# rotor.net
KiCad netlist of a schematic drawn in Altium Designer
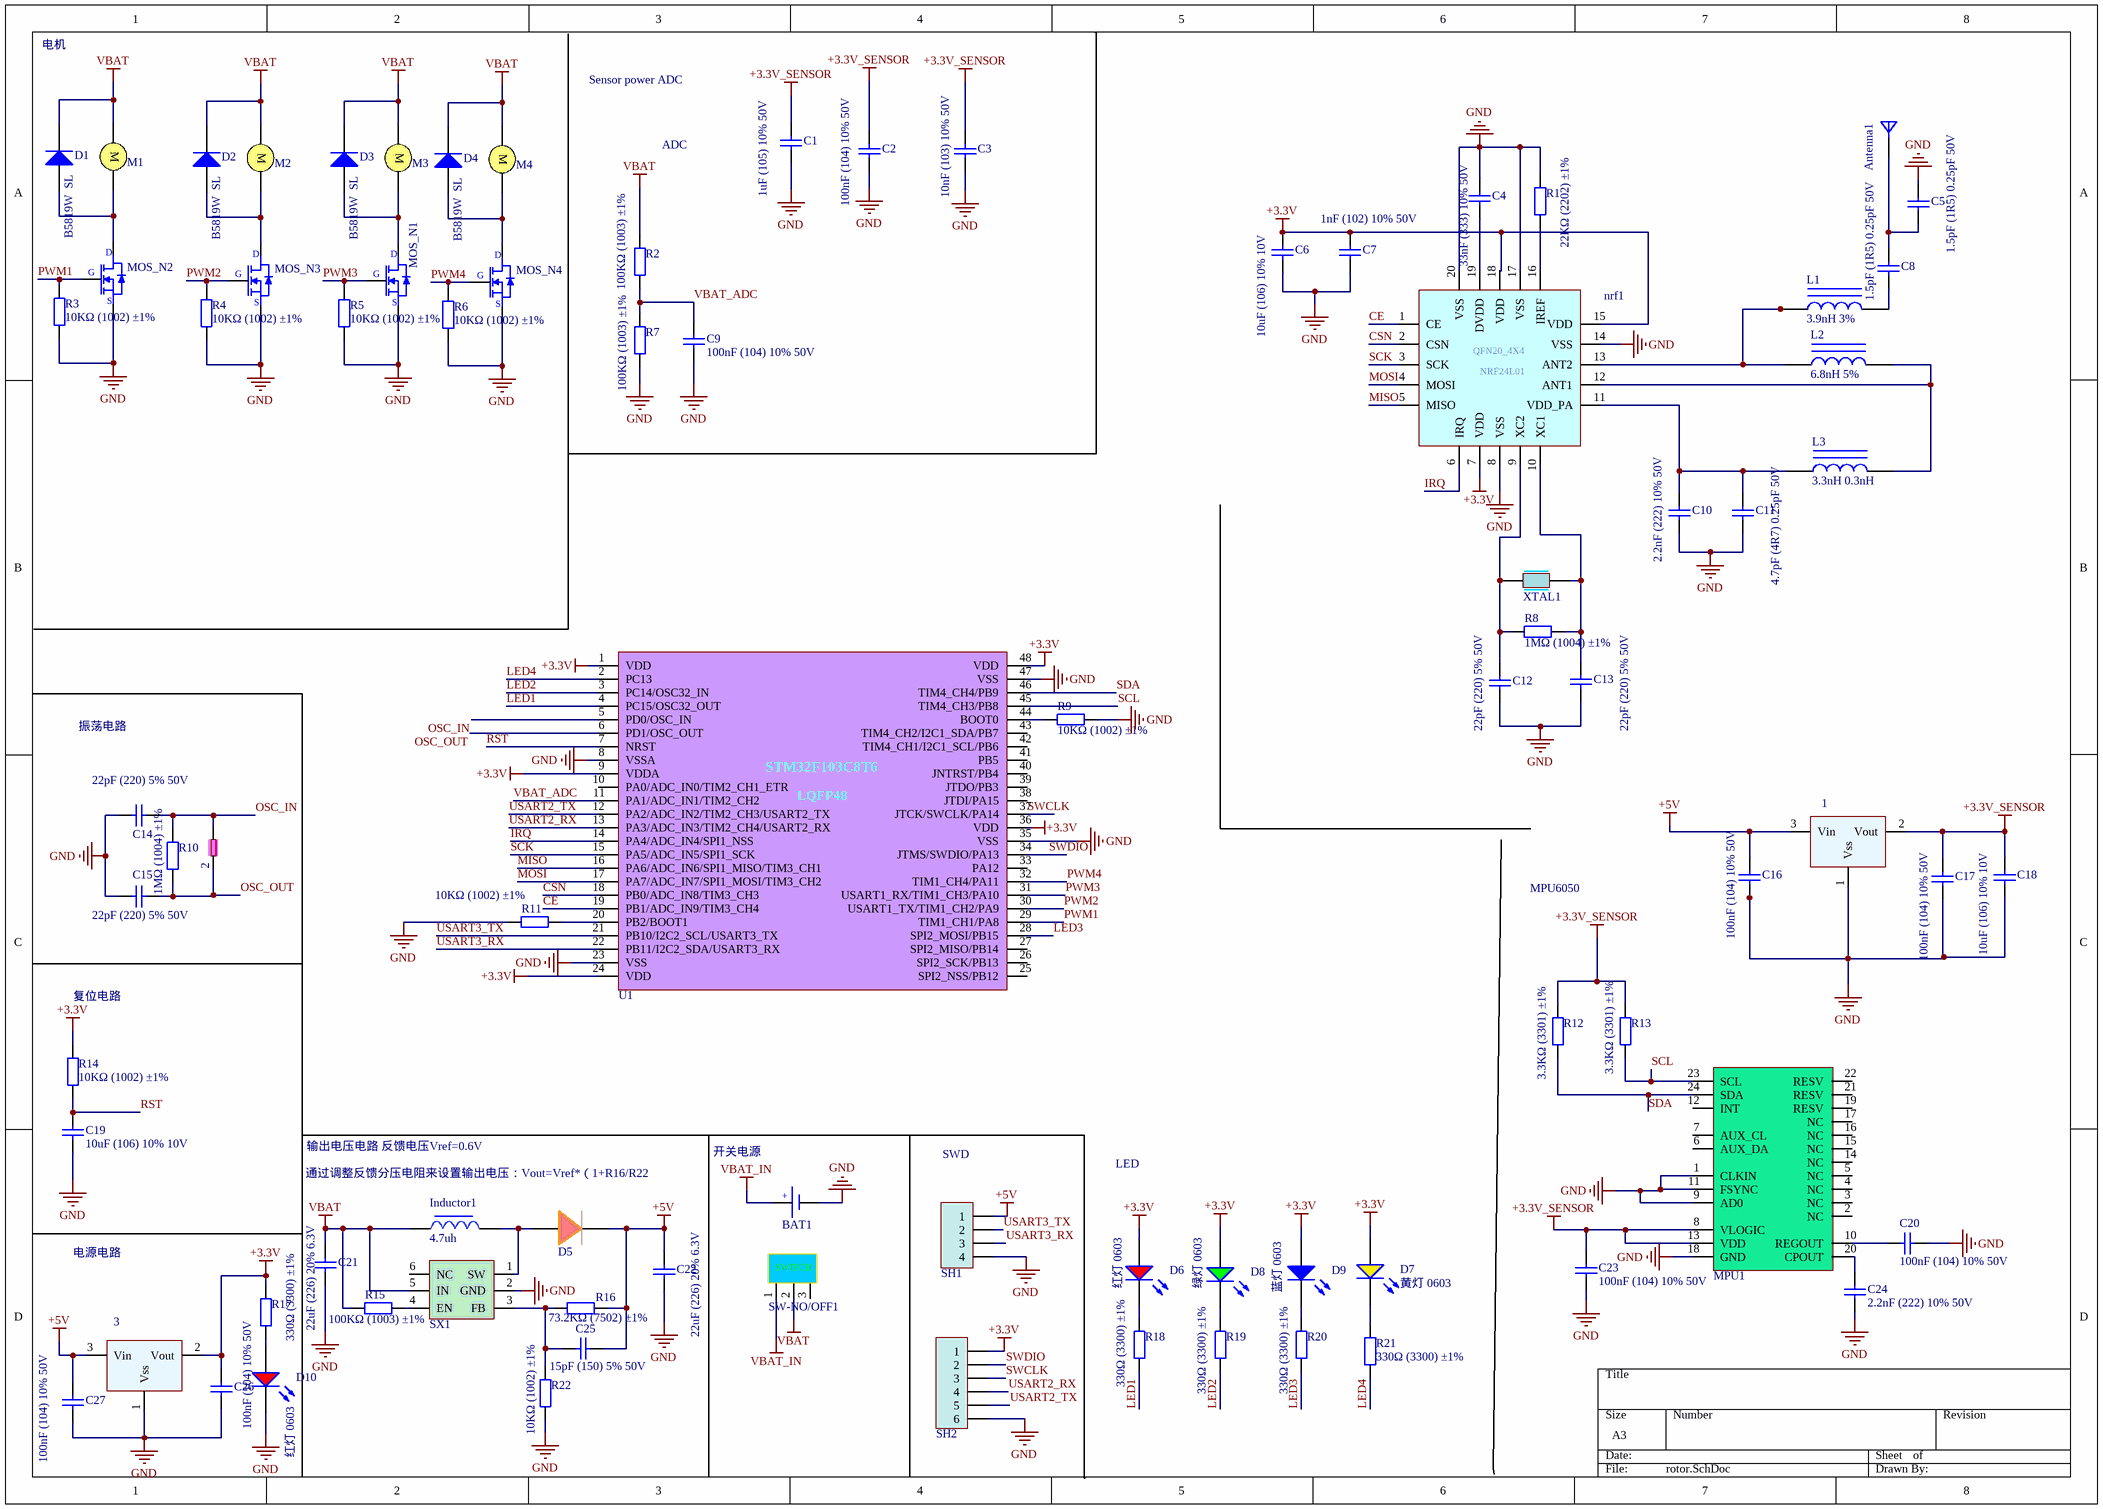
[diagram p0: rotor.SchDoc]

(export (version "E")
  (design (tool "Eeschema 10.0.6"))
  (components
    (comp (ref "1")
      (value "662K-3.3V(SOT-23-3)")
      (footprint "SOT-23-3")
      (libsource (lib "self_schlib v1.8.6") (part "662K-3.3V(SOT-23-3)"))
    )
    (comp (ref "2")
      (value "5032-8MHZ")
      (footprint "5032-8MHZ")
      (libsource (lib "self_schlib v1.8.6") (part "5032-8MHZ"))
    )
    (comp (ref "3")
      (value "662K-3.3V(SOT-23-3)")
      (footprint "SOT-23-3")
      (libsource (lib "self_schlib v1.8.6") (part "662K-3.3V(SOT-23-3)"))
    )
    (comp (ref "Antenna1")
      (value "Antenna")
      (footprint "Antenna")
      (libsource (lib "self_schlib v1.8.6") (part "Antenna"))
    )
    (comp (ref "BAT1") (value "BAT") (footprint "BAT") (libsource (lib "self_schlib v1.8.6") (part "BAT")))
    (comp (ref "C1")
      (value "1uF (105) 10% 50V")
      (footprint "0603_C")
      (description "贴片电容")
      (libsource (lib "Miscellaneous Devices Legend") (part "0603 1uF (105) 10% 50V"))
    )
    (comp (ref "C2")
      (value "100nF (104) 10% 50V")
      (footprint "0603_C")
      (description "贴片电容")
      (libsource (lib "Miscellaneous Devices Legend") (part "0603 100nF (104) 10% 50V"))
    )
    (comp (ref "C3")
      (value "10nF (103) 10% 50V")
      (footprint "0603_C")
      (description "贴片电容")
      (libsource (lib "Miscellaneous Devices Legend") (part "0603 10nF (103) 10% 50V"))
    )
    (comp (ref "C4")
      (value "33nF (333) 10% 50V")
      (footprint "0603_C")
      (description "贴片电容")
      (libsource (lib "Miscellaneous Devices Legend") (part "0603 33nF (333) 10% 50V"))
    )
    (comp (ref "C5")
      (value "1.5pF (1R5) 0.25pF 50V")
      (footprint "0402_C")
      (description "贴片电容")
      (libsource (lib "Miscellaneous Devices Legend") (part "0402 1.5pF (1R5) 0.25pF 50V"))
    )
    (comp (ref "C6")
      (value "10uF (106) 10% 10V")
      (footprint "0603_C")
      (description "贴片电容")
      (libsource (lib "Miscellaneous Devices Legend") (part "0603 10uF (106) 10% 10V"))
    )
    (comp (ref "C7")
      (value "1nF (102) 10% 50V")
      (footprint "0603_C")
      (description "贴片电容")
      (libsource (lib "Miscellaneous Devices Legend") (part "0603 1nF (102) 10% 50V"))
    )
    (comp (ref "C8")
      (value "1.5pF (1R5) 0.25pF 50V")
      (footprint "0402_C")
      (description "贴片电容")
      (libsource (lib "Miscellaneous Devices Legend") (part "0402 1.5pF (1R5) 0.25pF 50V"))
    )
    (comp (ref "C9")
      (value "100nF (104) 10% 50V")
      (footprint "0603_C")
      (description "贴片电容")
      (libsource (lib "Miscellaneous Devices Legend") (part "0603 100nF (104) 10% 50V"))
    )
    (comp (ref "C10")
      (value "2.2nF (222) 10% 50V")
      (footprint "0603_C")
      (description "贴片电容")
      (libsource (lib "Miscellaneous Devices Legend") (part "0603 2.2nF (222) 10% 50V"))
    )
    (comp (ref "C11")
      (value "4.7pF (4R7) 0.25pF 50V")
      (footprint "0603_C")
      (description "贴片电容")
      (libsource (lib "Miscellaneous Devices Legend") (part "0603 4.7pF (4R7) 0.25pF 50V"))
    )
    (comp (ref "C12")
      (value "22pF (220) 5% 50V")
      (footprint "0603_C")
      (description "贴片电容")
      (libsource (lib "Miscellaneous Devices Legend") (part "0603 22pF (220) 5% 50V"))
    )
    (comp (ref "C13")
      (value "22pF (220) 5% 50V")
      (footprint "0603_C")
      (description "贴片电容")
      (libsource (lib "Miscellaneous Devices Legend") (part "0603 22pF (220) 5% 50V"))
    )
    (comp (ref "C14")
      (value "22pF (220) 5% 50V")
      (footprint "0603_C")
      (description "贴片电容")
      (libsource (lib "Miscellaneous Devices Legend") (part "0603 22pF (220) 5% 50V"))
    )
    (comp (ref "C15")
      (value "22pF (220) 5% 50V")
      (footprint "0603_C")
      (description "贴片电容")
      (libsource (lib "Miscellaneous Devices Legend") (part "0603 22pF (220) 5% 50V"))
    )
    (comp (ref "C16")
      (value "100nF (104) 10% 50V")
      (footprint "0603_C")
      (description "贴片电容")
      (libsource (lib "Miscellaneous Devices Legend") (part "0603 100nF (104) 10% 50V"))
    )
    (comp (ref "C17")
      (value "100nF (104) 10% 50V")
      (footprint "0603_C")
      (description "贴片电容")
      (libsource (lib "Miscellaneous Devices Legend") (part "0603 100nF (104) 10% 50V"))
    )
    (comp (ref "C18")
      (value "10uF (106) 10% 10V")
      (footprint "0603_C")
      (description "贴片电容")
      (libsource (lib "Miscellaneous Devices Legend") (part "0603 10uF (106) 10% 10V"))
    )
    (comp (ref "C19")
      (value "10uF (106) 10% 10V")
      (footprint "0603_C")
      (description "贴片电容")
      (libsource (lib "Miscellaneous Devices Legend") (part "0603 10uF (106) 10% 10V"))
    )
    (comp (ref "C20")
      (value "100nF (104) 10% 50V")
      (footprint "0603_C")
      (description "贴片电容")
      (libsource (lib "Miscellaneous Devices Legend") (part "0603 100nF (104) 10% 50V"))
    )
    (comp (ref "C21")
      (value "22uF (226) 20% 6.3V")
      (footprint "0603_C")
      (description "贴片电容")
      (libsource (lib "Miscellaneous Devices Legend") (part "0603 22uF (226) 20% 6.3V"))
    )
    (comp (ref "C22")
      (value "22uF (226) 20% 6.3V")
      (footprint "0603_C")
      (description "贴片电容")
      (libsource (lib "Miscellaneous Devices Legend") (part "0603 22uF (226) 20% 6.3V"))
    )
    (comp (ref "C23")
      (value "100nF (104) 10% 50V")
      (footprint "0603_C")
      (description "贴片电容")
      (libsource (lib "Miscellaneous Devices Legend") (part "0603 100nF (104) 10% 50V"))
    )
    (comp (ref "C24")
      (value "2.2nF (222) 10% 50V")
      (footprint "0603_C")
      (description "贴片电容")
      (libsource (lib "Miscellaneous Devices Legend") (part "0603 2.2nF (222) 10% 50V"))
    )
    (comp (ref "C25")
      (value "15pF (150) 5% 50V")
      (footprint "0603_C")
      (description "贴片电容")
      (libsource (lib "Miscellaneous Devices Legend") (part "0603 15pF (150) 5% 50V"))
    )
    (comp (ref "C26")
      (value "100nF (104) 10% 50V")
      (footprint "0603_C")
      (description "贴片电容")
      (libsource (lib "Miscellaneous Devices Legend") (part "0603 100nF (104) 10% 50V"))
    )
    (comp (ref "C27")
      (value "100nF (104) 10% 50V")
      (footprint "0603_C")
      (description "贴片电容")
      (libsource (lib "Miscellaneous Devices Legend") (part "0603 100nF (104) 10% 50V"))
    )
    (comp (ref "D1")
      (value "B5819W  SL")
      (footprint "SOD-123")
      (description "肖特基二极管")
      (libsource (lib "Miscellaneous Devices Legend") (part "SOD-123 B5819W  SL"))
    )
    (comp (ref "D2")
      (value "B5819W  SL")
      (footprint "SOD-123")
      (description "肖特基二极管")
      (libsource (lib "Miscellaneous Devices Legend") (part "SOD-123 B5819W  SL"))
    )
    (comp (ref "D3")
      (value "B5819W  SL")
      (footprint "SOD-123")
      (description "肖特基二极管")
      (libsource (lib "Miscellaneous Devices Legend") (part "SOD-123 B5819W  SL"))
    )
    (comp (ref "D4")
      (value "B5819W  SL")
      (footprint "SOD-123")
      (description "肖特基二极管")
      (libsource (lib "Miscellaneous Devices Legend") (part "SOD-123 B5819W  SL"))
    )
    (comp (ref "D5")
      (value "SMA/DO-214")
      (footprint "SMA/DO-214")
      (libsource (lib "self_schlib v1.8.6") (part "SMA/DO-214"))
    )
    (comp (ref "D6")
      (value "红灯 0603")
      (footprint "0603_LED_S1")
      (description "发光二极管")
      (libsource (lib "Miscellaneous Devices Legend") (part "0603 红灯"))
    )
    (comp (ref "D7")
      (value "黄灯 0603")
      (footprint "0603_LED_S1")
      (description "发光二极管")
      (libsource (lib "Miscellaneous Devices Legend") (part "0603 黄灯"))
    )
    (comp (ref "D8")
      (value "绿灯 0603")
      (footprint "0603_LED_S1")
      (description "发光二极管")
      (libsource (lib "Miscellaneous Devices Legend") (part "0603 绿灯"))
    )
    (comp (ref "D9")
      (value "蓝灯 0603")
      (footprint "0603_LED_S1")
      (description "发光二极管")
      (libsource (lib "Miscellaneous Devices Legend") (part "0603 蓝灯"))
    )
    (comp (ref "D10")
      (value "红灯 0603")
      (footprint "0603_LED_S1")
      (description "发光二极管")
      (libsource (lib "Miscellaneous Devices Legend") (part "0603 红灯"))
    )
    (comp (ref "Inductor1")
      (value "Inductor")
      (footprint "CD32")
      (fields (field (name "ALTIUM_UNNAMED_1") "4.7uh"))
      (libsource (lib "self_schlib v1.8.6") (part "Inductor"))
    )
    (comp (ref "L1")
      (value "3.9nH 3%")
      (footprint "0402_L")
      (description "贴片电感")
      (libsource (lib "Miscellaneous Devices Legend") (part "0402 3.9nH 3%"))
    )
    (comp (ref "L2")
      (value "6.8nH 5%")
      (footprint "0402_L")
      (description "贴片电感")
      (libsource (lib "Miscellaneous Devices Legend") (part "0402 6.8nH 5%"))
    )
    (comp (ref "L3")
      (value "3.3nH 0.3nH")
      (footprint "0402_L")
      (description "贴片电感")
      (libsource (lib "Miscellaneous Devices Legend") (part "0402 3.3nH 0.3nH"))
    )
    (comp (ref "M1") (value "MOTO") (footprint "MOTO") (libsource (lib "self_schlib v1.8.6") (part "MOTO")))
    (comp (ref "M2") (value "MOTO") (footprint "MOTO") (libsource (lib "self_schlib v1.8.6") (part "MOTO")))
    (comp (ref "M3") (value "MOTO") (footprint "MOTO") (libsource (lib "self_schlib v1.8.6") (part "MOTO")))
    (comp (ref "M4") (value "MOTO") (footprint "MOTO") (libsource (lib "self_schlib v1.8.6") (part "MOTO")))
    (comp (ref "MOS_N1")
      (value "MOS_N")
      (footprint "SOT-23-3")
      (libsource (lib "self_schlib v1.8.6") (part "MOS_N_(SOT-23-3)"))
    )
    (comp (ref "MOS_N2")
      (value "MOS_N")
      (footprint "SOT-23-3")
      (libsource (lib "self_schlib v1.8.6") (part "MOS_N_(SOT-23-3)"))
    )
    (comp (ref "MOS_N3")
      (value "MOS_N")
      (footprint "SOT-23-3")
      (libsource (lib "self_schlib v1.8.6") (part "MOS_N_(SOT-23-3)"))
    )
    (comp (ref "MOS_N4")
      (value "MOS_N")
      (footprint "SOT-23-3")
      (libsource (lib "self_schlib v1.8.6") (part "MOS_N_(SOT-23-3)"))
    )
    (comp (ref "MPU1")
      (value "MPU6050")
      (footprint "QFN24_4X4")
      (libsource (lib "self_schlib v1.8.6") (part "MPU6050(QFN24_4X4)"))
    )
    (comp (ref "nrf1")
      (value "nrf24l01")
      (footprint "QFN20_4X4")
      (libsource (lib "self_schlib v1.8.6") (part "QFN20-4X4"))
    )
    (comp (ref "R1")
      (value "22KΩ (2202) ±1%")
      (footprint "0603_R")
      (description "贴片电阻")
      (libsource (lib "Miscellaneous Devices Legend") (part "0603 22KΩ (2202) 1%"))
    )
    (comp (ref "R2")
      (value "100KΩ (1003) ±1%")
      (footprint "0603_R")
      (description "贴片电阻")
      (libsource (lib "") (part "0603 100KΩ (1003) 1%_1"))
    )
    (comp (ref "R3")
      (value "10KΩ (1002) ±1%")
      (footprint "0603_R")
      (description "贴片电阻")
      (libsource (lib "Miscellaneous Devices Legend") (part "0603 10KΩ (1002) 1%"))
    )
    (comp (ref "R4")
      (value "10KΩ (1002) ±1%")
      (footprint "0603_R")
      (description "贴片电阻")
      (libsource (lib "Miscellaneous Devices Legend") (part "0603 10KΩ (1002) 1%"))
    )
    (comp (ref "R5")
      (value "10KΩ (1002) ±1%")
      (footprint "0603_R")
      (description "贴片电阻")
      (libsource (lib "Miscellaneous Devices Legend") (part "0603 10KΩ (1002) 1%"))
    )
    (comp (ref "R6")
      (value "10KΩ (1002) ±1%")
      (footprint "0603_R")
      (description "贴片电阻")
      (libsource (lib "Miscellaneous Devices Legend") (part "0603 10KΩ (1002) 1%"))
    )
    (comp (ref "R7")
      (value "100KΩ (1003) ±1%")
      (footprint "0603_R")
      (description "贴片电阻")
      (libsource (lib "") (part "0603 100KΩ (1003) 1%_1"))
    )
    (comp (ref "R8")
      (value "1MΩ (1004) ±1%")
      (footprint "0603_R")
      (description "贴片电阻")
      (libsource (lib "Miscellaneous Devices Legend") (part "0603 1MΩ (1004) 1%"))
    )
    (comp (ref "R9")
      (value "10KΩ (1002) ±1%")
      (footprint "0603_R")
      (description "贴片电阻")
      (libsource (lib "") (part "0603 10KΩ (1002) 1%_2"))
    )
    (comp (ref "R10")
      (value "1MΩ (1004) ±1%")
      (footprint "0603_R")
      (description "贴片电阻")
      (libsource (lib "") (part "0603 1MΩ (1004) 1%_1"))
    )
    (comp (ref "R11")
      (value "10KΩ (1002) ±1%")
      (footprint "0603_R")
      (description "贴片电阻")
      (libsource (lib "") (part "0603 10KΩ (1002) 1%_1"))
    )
    (comp (ref "R12")
      (value "3.3KΩ (3301) ±1%")
      (footprint "0603_R")
      (description "贴片电阻")
      (libsource (lib "Miscellaneous Devices Legend") (part "0603 3.3KΩ (3301) 1%"))
    )
    (comp (ref "R13")
      (value "3.3KΩ (3301) ±1%")
      (footprint "0603_R")
      (description "贴片电阻")
      (libsource (lib "Miscellaneous Devices Legend") (part "0603 3.3KΩ (3301) 1%"))
    )
    (comp (ref "R14")
      (value "10KΩ (1002) ±1%")
      (footprint "0603_R")
      (description "贴片电阻")
      (libsource (lib "Miscellaneous Devices Legend") (part "0603 10KΩ (1002) 1%"))
    )
    (comp (ref "R15")
      (value "100KΩ (1003) ±1%")
      (footprint "0603_R")
      (description "贴片电阻")
      (libsource (lib "Miscellaneous Devices Legend") (part "0603 100KΩ (1003) 1%"))
    )
    (comp (ref "R16")
      (value "73.2KΩ (7502) ±1%")
      (footprint "0603_R")
      (description "贴片电阻")
      (libsource (lib "Miscellaneous Devices Legend") (part "0603 75KΩ (7502) 1%"))
    )
    (comp (ref "R17")
      (value "330Ω (3300) ±1%")
      (footprint "0603_R")
      (description "贴片电阻")
      (libsource (lib "Miscellaneous Devices Legend") (part "0603 330Ω (3300) 1%"))
    )
    (comp (ref "R18")
      (value "330Ω (3300) ±1%")
      (footprint "0603_R")
      (description "贴片电阻")
      (libsource (lib "Miscellaneous Devices Legend") (part "0603 330Ω (3300) 1%"))
    )
    (comp (ref "R19")
      (value "330Ω (3300) ±1%")
      (footprint "0603_R")
      (description "贴片电阻")
      (libsource (lib "Miscellaneous Devices Legend") (part "0603 330Ω (3300) 1%"))
    )
    (comp (ref "R20")
      (value "330Ω (3300) ±1%")
      (footprint "0603_R")
      (description "贴片电阻")
      (libsource (lib "Miscellaneous Devices Legend") (part "0603 330Ω (3300) 1%"))
    )
    (comp (ref "R21")
      (value "330Ω (3300) ±1%")
      (footprint "0603_R")
      (description "贴片电阻")
      (libsource (lib "Miscellaneous Devices Legend") (part "0603 330Ω (3300) 1%"))
    )
    (comp (ref "R22")
      (value "10KΩ (1002) ±1%")
      (footprint "0603_R")
      (description "贴片电阻")
      (libsource (lib "Miscellaneous Devices Legend") (part "0603 10KΩ (1002) 1%"))
    )
    (comp (ref "SH1")
      (value "SH1.0mm-4PIN")
      (footprint "SH1.0mm-4PIN")
      (libsource (lib "self_schlib v1.8.6") (part "SH1.0mm-4PIN"))
    )
    (comp (ref "SH2")
      (value "SH1.0mm-6PIN")
      (footprint "SH1.0mm-6PIN")
      (libsource (lib "self_schlib v1.8.6") (part "SH1.0mm-6PIN"))
    )
    (comp (ref "SW-NO/OFF1")
      (value "SW-NO/OFF")
      (footprint "SW-NO/OFF-PIN3")
      (libsource (lib "self_schlib v1.8.6") (part "SW-NO/OFF-PIN3"))
    )
    (comp (ref "SX1")
      (value "SX1308")
      (footprint "SX1308")
      (libsource (lib "self_schlib v1.8.6") (part "SX1308"))
    )
    (comp (ref "U1")
      (value "STM32F103C8T6")
      (footprint "STM32F103C8T6")
      (libsource (lib "self_schlib v1.8.6") (part "STM32F103C8T6"))
    )
    (comp (ref "XTAL1")
      (value "Crystal Oscillator 3225")
      (footprint "Crystal Oscillator 3225")
      (libsource (lib "self_schlib v1.8.6") (part "Crystal Oscillator 3225"))
    )
  )
  (nets
    (net (code "1") (name "+3.3V") (class "Default")
      (node (ref "3") (pin "2") (pinfunction "Vout_2") (pintype "passive"))
      (node (ref "C26") (pin "2") (pinfunction "2_2") (pintype "passive"))
      (node (ref "C6") (pin "2") (pinfunction "2_2") (pintype "passive"))
      (node (ref "C7") (pin "2") (pinfunction "2_2") (pintype "passive"))
      (node (ref "D6") (pin "A") (pinfunction "A_A") (pintype "passive"))
      (node (ref "D7") (pin "A") (pinfunction "A_A") (pintype "passive"))
      (node (ref "D8") (pin "A") (pinfunction "A_A") (pintype "passive"))
      (node (ref "D9") (pin "A") (pinfunction "A_A") (pintype "passive"))
      (node (ref "R14") (pin "2") (pinfunction "2_2") (pintype "passive"))
      (node (ref "R17") (pin "2") (pinfunction "2_2") (pintype "passive"))
      (node (ref "SH2") (pin "1") (pinfunction "1_1") (pintype "passive"))
      (node (ref "U1") (pin "1") (pinfunction "VDD_1") (pintype "passive"))
      (node (ref "U1") (pin "24") (pinfunction "VDD_24") (pintype "passive"))
      (node (ref "U1") (pin "36") (pinfunction "VDD_36") (pintype "passive"))
      (node (ref "U1") (pin "48") (pinfunction "VDD_48") (pintype "passive"))
      (node (ref "U1") (pin "9") (pinfunction "VDDA_9") (pintype "passive"))
      (node (ref "nrf1") (pin "15") (pinfunction "VDD_15") (pintype "passive"))
      (node (ref "nrf1") (pin "7") (pinfunction "VDD_7") (pintype "passive"))
    )
    (net (code "2") (name "+3.3V_SENSOR") (class "Default")
      (node (ref "1") (pin "2") (pinfunction "Vout_2") (pintype "passive"))
      (node (ref "C1") (pin "2") (pinfunction "2_2") (pintype "passive"))
      (node (ref "C17") (pin "2") (pinfunction "2_2") (pintype "passive"))
      (node (ref "C18") (pin "2") (pinfunction "2_2") (pintype "passive"))
      (node (ref "C2") (pin "2") (pinfunction "2_2") (pintype "passive"))
      (node (ref "C23") (pin "2") (pinfunction "2_2") (pintype "passive"))
      (node (ref "C3") (pin "2") (pinfunction "2_2") (pintype "passive"))
      (node (ref "MPU1") (pin "13") (pinfunction "VDD_13") (pintype "passive"))
      (node (ref "MPU1") (pin "8") (pinfunction "VLOGIC_8") (pintype "passive"))
      (node (ref "R12") (pin "2") (pinfunction "2_2") (pintype "passive"))
      (node (ref "R13") (pin "2") (pinfunction "2_2") (pintype "passive"))
    )
    (net (code "3") (name "+5V") (class "Default")
      (node (ref "1") (pin "3") (pinfunction "Vin_3") (pintype "passive"))
      (node (ref "3") (pin "3") (pinfunction "Vin_3") (pintype "passive"))
      (node (ref "C16") (pin "2") (pinfunction "2_2") (pintype "passive"))
      (node (ref "C22") (pin "2") (pinfunction "2_2") (pintype "passive"))
      (node (ref "C25") (pin "2") (pinfunction "2_2") (pintype "passive"))
      (node (ref "C27") (pin "2") (pinfunction "2_2") (pintype "passive"))
      (node (ref "D5") (pin "2") (pinfunction "2_2") (pintype "passive"))
      (node (ref "R16") (pin "2") (pinfunction "2_2") (pintype "passive"))
      (node (ref "SH1") (pin "1") (pinfunction "1_1") (pintype "passive"))
    )
    (net (code "4") (name "/CE") (class "Default")
      (node (ref "U1") (pin "19") (pinfunction "PB1/ADC_IN9/TIM3_CH4_19") (pintype "passive"))
      (node (ref "nrf1") (pin "1") (pinfunction "CE_1") (pintype "passive"))
    )
    (net (code "5") (name "/CSN") (class "Default")
      (node (ref "U1") (pin "18") (pinfunction "PB0/ADC_IN8/TIM3_CH3_18") (pintype "passive"))
      (node (ref "nrf1") (pin "2") (pinfunction "CSN_2") (pintype "passive"))
    )
    (net (code "6") (name "/IRQ") (class "Default")
      (node (ref "U1") (pin "14") (pinfunction "PA4/ADC_IN4/SPI1_NSS_14") (pintype "passive"))
      (node (ref "nrf1") (pin "6") (pinfunction "IRQ_6") (pintype "passive"))
    )
    (net (code "7") (name "/LED1") (class "Default")
      (node (ref "R18") (pin "1") (pinfunction "1_1") (pintype "passive"))
      (node (ref "U1") (pin "4") (pinfunction "PC15/OSC32_OUT_4") (pintype "passive"))
    )
    (net (code "8") (name "/LED2") (class "Default")
      (node (ref "R19") (pin "1") (pinfunction "1_1") (pintype "passive"))
      (node (ref "U1") (pin "3") (pinfunction "PC14/OSC32_IN_3") (pintype "passive"))
    )
    (net (code "9") (name "/LED3") (class "Default")
      (node (ref "R20") (pin "1") (pinfunction "1_1") (pintype "passive"))
      (node (ref "U1") (pin "28") (pinfunction "SPI2_MOSI/PB15_28") (pintype "passive"))
    )
    (net (code "10") (name "/LED4") (class "Default")
      (node (ref "R21") (pin "1") (pinfunction "1_1") (pintype "passive"))
      (node (ref "U1") (pin "2") (pinfunction "PC13_2") (pintype "passive"))
    )
    (net (code "11") (name "/MISO") (class "Default")
      (node (ref "U1") (pin "16") (pinfunction "PA6/ADC_IN6/SPI1_MISO/TIM3_CH1_16") (pintype "passive"))
      (node (ref "nrf1") (pin "5") (pinfunction "MISO_5") (pintype "passive"))
    )
    (net (code "12") (name "/MOSI") (class "Default")
      (node (ref "U1") (pin "17") (pinfunction "PA7/ADC_IN7/SPI1_MOSI/TIM3_CH2_17") (pintype "passive"))
      (node (ref "nrf1") (pin "4") (pinfunction "MOSI_4") (pintype "passive"))
    )
    (net (code "13") (name "/OSC_IN") (class "Default")
      (node (ref "2") (pin "3") (pinfunction "3_3") (pintype "passive"))
      (node (ref "C14") (pin "2") (pinfunction "2_2") (pintype "passive"))
      (node (ref "R10") (pin "2") (pinfunction "2_2") (pintype "passive"))
      (node (ref "U1") (pin "5") (pinfunction "PD0/OSC_IN_5") (pintype "passive"))
    )
    (net (code "14") (name "/OSC_OUT") (class "Default")
      (node (ref "2") (pin "1") (pinfunction "1_1") (pintype "passive"))
      (node (ref "C15") (pin "2") (pinfunction "2_2") (pintype "passive"))
      (node (ref "R10") (pin "1") (pinfunction "1_1") (pintype "passive"))
      (node (ref "U1") (pin "6") (pinfunction "PD1/OSC_OUT_6") (pintype "passive"))
    )
    (net (code "15") (name "/PWM1") (class "Default")
      (node (ref "MOS_N2") (pin "1") (pinfunction "G_1") (pintype "passive"))
      (node (ref "R3") (pin "2") (pinfunction "2_2") (pintype "passive"))
      (node (ref "U1") (pin "29") (pinfunction "TIM1_CH1/PA8_29") (pintype "passive"))
    )
    (net (code "16") (name "/PWM2") (class "Default")
      (node (ref "MOS_N3") (pin "1") (pinfunction "G_1") (pintype "passive"))
      (node (ref "R4") (pin "2") (pinfunction "2_2") (pintype "passive"))
      (node (ref "U1") (pin "30") (pinfunction "USART1_TX/TIM1_CH2/PA9_30") (pintype "passive"))
    )
    (net (code "17") (name "/PWM3") (class "Default")
      (node (ref "MOS_N1") (pin "1") (pinfunction "G_1") (pintype "passive"))
      (node (ref "R5") (pin "2") (pinfunction "2_2") (pintype "passive"))
      (node (ref "U1") (pin "31") (pinfunction "USART1_RX/TIM1_CH3/PA10_31") (pintype "passive"))
    )
    (net (code "18") (name "/PWM4") (class "Default")
      (node (ref "MOS_N4") (pin "1") (pinfunction "G_1") (pintype "passive"))
      (node (ref "R6") (pin "2") (pinfunction "2_2") (pintype "passive"))
      (node (ref "U1") (pin "32") (pinfunction "TIM1_CH4/PA11_32") (pintype "passive"))
    )
    (net (code "19") (name "/RST") (class "Default")
      (node (ref "C19") (pin "2") (pinfunction "2_2") (pintype "passive"))
      (node (ref "R14") (pin "1") (pinfunction "1_1") (pintype "passive"))
      (node (ref "U1") (pin "7") (pinfunction "NRST_7") (pintype "passive"))
    )
    (net (code "20") (name "/SCK") (class "Default")
      (node (ref "U1") (pin "15") (pinfunction "PA5/ADC_IN5/SPI1_SCK_15") (pintype "passive"))
      (node (ref "nrf1") (pin "3") (pinfunction "SCK_3") (pintype "passive"))
    )
    (net (code "21") (name "/SCL") (class "Default")
      (node (ref "MPU1") (pin "23") (pinfunction "SCL_23") (pintype "passive"))
      (node (ref "R13") (pin "1") (pinfunction "1_1") (pintype "passive"))
      (node (ref "U1") (pin "45") (pinfunction "TIM4_CH3/PB8_45") (pintype "passive"))
    )
    (net (code "22") (name "/SDA") (class "Default")
      (node (ref "MPU1") (pin "24") (pinfunction "SDA_24") (pintype "passive"))
      (node (ref "R12") (pin "1") (pinfunction "1_1") (pintype "passive"))
      (node (ref "U1") (pin "46") (pinfunction "TIM4_CH4/PB9_46") (pintype "passive"))
    )
    (net (code "23") (name "/SWCLK") (class "Default")
      (node (ref "SH2") (pin "3") (pinfunction "3_3") (pintype "passive"))
      (node (ref "U1") (pin "37") (pinfunction "JTCK/SWCLK/PA14_37") (pintype "passive"))
    )
    (net (code "24") (name "/SWDIO") (class "Default")
      (node (ref "SH2") (pin "2") (pinfunction "2_2") (pintype "passive"))
      (node (ref "U1") (pin "34") (pinfunction "JTMS/SWDIO/PA13_34") (pintype "passive"))
    )
    (net (code "25") (name "/USART2_RX") (class "Default")
      (node (ref "SH2") (pin "4") (pinfunction "4_4") (pintype "passive"))
      (node (ref "U1") (pin "13") (pinfunction "PA3/ADC_IN3/TIM2_CH4/USART2_RX_13") (pintype "passive"))
    )
    (net (code "26") (name "/USART2_TX") (class "Default")
      (node (ref "SH2") (pin "5") (pinfunction "5_5") (pintype "passive"))
      (node (ref "U1") (pin "12") (pinfunction "PA2/ADC_IN2/TIM2_CH3/USART2_TX_12") (pintype "passive"))
    )
    (net (code "27") (name "/USART3_RX") (class "Default")
      (node (ref "SH1") (pin "3") (pinfunction "3_3") (pintype "passive"))
      (node (ref "U1") (pin "22") (pinfunction "PB11/I2C2_SDA/USART3_RX_22") (pintype "passive"))
    )
    (net (code "28") (name "/USART3_TX") (class "Default")
      (node (ref "SH1") (pin "2") (pinfunction "2_2") (pintype "passive"))
      (node (ref "U1") (pin "21") (pinfunction "PB10/I2C2_SCL/USART3_TX_21") (pintype "passive"))
    )
    (net (code "29") (name "/VBAT_ADC") (class "Default")
      (node (ref "C9") (pin "2") (pinfunction "2_2") (pintype "passive"))
      (node (ref "R2") (pin "1") (pinfunction "1_1") (pintype "passive"))
      (node (ref "R7") (pin "2") (pinfunction "2_2") (pintype "passive"))
      (node (ref "U1") (pin "11") (pinfunction "PA1/ADC_IN1/TIM2_CH2_11") (pintype "passive"))
    )
    (net (code "30") (name "GND") (class "Default")
      (node (ref "1") (pin "1") (pinfunction "Vss_1") (pintype "passive"))
      (node (ref "3") (pin "1") (pinfunction "Vss_1") (pintype "passive"))
      (node (ref "BAT1") (pin "2") (pinfunction "-_2") (pintype "passive"))
      (node (ref "C1") (pin "1") (pinfunction "1_1") (pintype "passive"))
      (node (ref "C10") (pin "1") (pinfunction "1_1") (pintype "passive"))
      (node (ref "C11") (pin "1") (pinfunction "1_1") (pintype "passive"))
      (node (ref "C12") (pin "1") (pinfunction "1_1") (pintype "passive"))
      (node (ref "C13") (pin "1") (pinfunction "1_1") (pintype "passive"))
      (node (ref "C14") (pin "1") (pinfunction "1_1") (pintype "passive"))
      (node (ref "C15") (pin "1") (pinfunction "1_1") (pintype "passive"))
      (node (ref "C16") (pin "1") (pinfunction "1_1") (pintype "passive"))
      (node (ref "C17") (pin "1") (pinfunction "1_1") (pintype "passive"))
      (node (ref "C18") (pin "1") (pinfunction "1_1") (pintype "passive"))
      (node (ref "C19") (pin "1") (pinfunction "1_1") (pintype "passive"))
      (node (ref "C2") (pin "1") (pinfunction "1_1") (pintype "passive"))
      (node (ref "C20") (pin "2") (pinfunction "2_2") (pintype "passive"))
      (node (ref "C21") (pin "1") (pinfunction "1_1") (pintype "passive"))
      (node (ref "C22") (pin "1") (pinfunction "1_1") (pintype "passive"))
      (node (ref "C23") (pin "1") (pinfunction "1_1") (pintype "passive"))
      (node (ref "C24") (pin "1") (pinfunction "1_1") (pintype "passive"))
      (node (ref "C26") (pin "1") (pinfunction "1_1") (pintype "passive"))
      (node (ref "C27") (pin "1") (pinfunction "1_1") (pintype "passive"))
      (node (ref "C3") (pin "1") (pinfunction "1_1") (pintype "passive"))
      (node (ref "C4") (pin "2") (pinfunction "2_2") (pintype "passive"))
      (node (ref "C5") (pin "2") (pinfunction "2_2") (pintype "passive"))
      (node (ref "C6") (pin "1") (pinfunction "1_1") (pintype "passive"))
      (node (ref "C7") (pin "1") (pinfunction "1_1") (pintype "passive"))
      (node (ref "C9") (pin "1") (pinfunction "1_1") (pintype "passive"))
      (node (ref "D10") (pin "K") (pinfunction "K_K") (pintype "passive"))
      (node (ref "MOS_N1") (pin "2") (pinfunction "S_2") (pintype "passive"))
      (node (ref "MOS_N2") (pin "2") (pinfunction "S_2") (pintype "passive"))
      (node (ref "MOS_N3") (pin "2") (pinfunction "S_2") (pintype "passive"))
      (node (ref "MOS_N4") (pin "2") (pinfunction "S_2") (pintype "passive"))
      (node (ref "MPU1") (pin "1") (pinfunction "CLKIN_1") (pintype "passive"))
      (node (ref "MPU1") (pin "11") (pinfunction "FSYNC_11") (pintype "passive"))
      (node (ref "MPU1") (pin "18") (pinfunction "GND_18") (pintype "passive"))
      (node (ref "MPU1") (pin "9") (pinfunction "AD0_9") (pintype "passive"))
      (node (ref "R1") (pin "2") (pinfunction "2_2") (pintype "passive"))
      (node (ref "R11") (pin "2") (pinfunction "2_2") (pintype "passive"))
      (node (ref "R22") (pin "1") (pinfunction "1_1") (pintype "passive"))
      (node (ref "R3") (pin "1") (pinfunction "1_1") (pintype "passive"))
      (node (ref "R4") (pin "1") (pinfunction "1_1") (pintype "passive"))
      (node (ref "R5") (pin "1") (pinfunction "1_1") (pintype "passive"))
      (node (ref "R6") (pin "1") (pinfunction "1_1") (pintype "passive"))
      (node (ref "R7") (pin "1") (pinfunction "1_1") (pintype "passive"))
      (node (ref "R9") (pin "2") (pinfunction "2_2") (pintype "passive"))
      (node (ref "SH1") (pin "4") (pinfunction "4_4") (pintype "passive"))
      (node (ref "SH2") (pin "6") (pinfunction "6_6") (pintype "passive"))
      (node (ref "SX1") (pin "2") (pinfunction "GND_2") (pintype "passive"))
      (node (ref "U1") (pin "23") (pinfunction "VSS_23") (pintype "passive"))
      (node (ref "U1") (pin "35") (pinfunction "VSS_35") (pintype "passive"))
      (node (ref "U1") (pin "47") (pinfunction "VSS_47") (pintype "passive"))
      (node (ref "U1") (pin "8") (pinfunction "VSSA_8") (pintype "passive"))
      (node (ref "nrf1") (pin "14") (pinfunction "VSS_14") (pintype "passive"))
      (node (ref "nrf1") (pin "17") (pinfunction "VSS_17") (pintype "passive"))
      (node (ref "nrf1") (pin "20") (pinfunction "VSS_20") (pintype "passive"))
      (node (ref "nrf1") (pin "8") (pinfunction "VSS_8") (pintype "passive"))
    )
    (net (code "31") (name "Net-(Antenna1-Pad1)") (class "Default")
      (node (ref "Antenna1") (pin "1") (pinfunction "1_1") (pintype "passive"))
      (node (ref "C5") (pin "1") (pinfunction "1_1") (pintype "passive"))
      (node (ref "C8") (pin "2") (pinfunction "2_2") (pintype "passive"))
    )
    (net (code "32") (name "Net-(C8-Pad1)") (class "Default")
      (node (ref "C8") (pin "1") (pinfunction "1_1") (pintype "passive"))
      (node (ref "L1") (pin "2") (pinfunction "2_2") (pintype "passive"))
    )
    (net (code "33") (name "Net-(D1-A)") (class "Default")
      (node (ref "D1") (pin "1") (pinfunction "A_1") (pintype "passive"))
      (node (ref "M1") (pin "2") (pinfunction "2_2") (pintype "tri_state"))
      (node (ref "MOS_N2") (pin "3") (pinfunction "D_3") (pintype "passive"))
    )
    (net (code "34") (name "Net-(D2-A)") (class "Default")
      (node (ref "D2") (pin "1") (pinfunction "A_1") (pintype "passive"))
      (node (ref "M2") (pin "2") (pinfunction "2_2") (pintype "tri_state"))
      (node (ref "MOS_N3") (pin "3") (pinfunction "D_3") (pintype "passive"))
    )
    (net (code "35") (name "Net-(D3-A)") (class "Default")
      (node (ref "D3") (pin "1") (pinfunction "A_1") (pintype "passive"))
      (node (ref "M3") (pin "2") (pinfunction "2_2") (pintype "tri_state"))
      (node (ref "MOS_N1") (pin "3") (pinfunction "D_3") (pintype "passive"))
    )
    (net (code "36") (name "Net-(D4-A)") (class "Default")
      (node (ref "D4") (pin "1") (pinfunction "A_1") (pintype "passive"))
      (node (ref "M4") (pin "2") (pinfunction "2_2") (pintype "tri_state"))
      (node (ref "MOS_N4") (pin "3") (pinfunction "D_3") (pintype "passive"))
    )
    (net (code "37") (name "Net-(D6-PadK)") (class "Default")
      (node (ref "D6") (pin "K") (pinfunction "K_K") (pintype "passive"))
      (node (ref "R18") (pin "2") (pinfunction "2_2") (pintype "passive"))
    )
    (net (code "38") (name "Net-(D7-PadK)") (class "Default")
      (node (ref "D7") (pin "K") (pinfunction "K_K") (pintype "passive"))
      (node (ref "R21") (pin "2") (pinfunction "2_2") (pintype "passive"))
    )
    (net (code "39") (name "Net-(D8-PadK)") (class "Default")
      (node (ref "D8") (pin "K") (pinfunction "K_K") (pintype "passive"))
      (node (ref "R19") (pin "2") (pinfunction "2_2") (pintype "passive"))
    )
    (net (code "40") (name "Net-(D9-PadK)") (class "Default")
      (node (ref "D9") (pin "K") (pinfunction "K_K") (pintype "passive"))
      (node (ref "R20") (pin "2") (pinfunction "2_2") (pintype "passive"))
    )
    (net (code "41") (name "Net-(D10-PadA)") (class "Default")
      (node (ref "D10") (pin "A") (pinfunction "A_A") (pintype "passive"))
      (node (ref "R17") (pin "1") (pinfunction "1_1") (pintype "passive"))
    )
    (net (code "42") (name "Net-(MPU1-CPOUT)") (class "Default")
      (node (ref "C24") (pin "2") (pinfunction "2_2") (pintype "passive"))
      (node (ref "MPU1") (pin "20") (pinfunction "CPOUT_20") (pintype "passive"))
    )
    (net (code "43") (name "Net-(MPU1-REGOUT)") (class "Default")
      (node (ref "C20") (pin "1") (pinfunction "1_1") (pintype "passive"))
      (node (ref "MPU1") (pin "10") (pinfunction "REGOUT_10") (pintype "passive"))
    )
    (net (code "44") (name "Net-(SX1-EN)") (class "Default")
      (node (ref "R15") (pin "2") (pinfunction "2_2") (pintype "passive"))
      (node (ref "SX1") (pin "4") (pinfunction "EN_4") (pintype "passive"))
    )
    (net (code "45") (name "Net-(SX1-FB)") (class "Default")
      (node (ref "C25") (pin "1") (pinfunction "1_1") (pintype "passive"))
      (node (ref "R16") (pin "1") (pinfunction "1_1") (pintype "passive"))
      (node (ref "R22") (pin "2") (pinfunction "2_2") (pintype "passive"))
      (node (ref "SX1") (pin "3") (pinfunction "FB_3") (pintype "passive"))
    )
    (net (code "46") (name "Net-(SX1-SW)") (class "Default")
      (node (ref "D5") (pin "1") (pinfunction "1_1") (pintype "passive"))
      (node (ref "Inductor1") (pin "2") (pinfunction "2_2") (pintype "passive"))
      (node (ref "SX1") (pin "1") (pinfunction "SW_1") (pintype "passive"))
    )
    (net (code "47") (name "Net-(U1-BOOT0)") (class "Default")
      (node (ref "R9") (pin "1") (pinfunction "1_1") (pintype "passive"))
      (node (ref "U1") (pin "44") (pinfunction "BOOT0_44") (pintype "passive"))
    )
    (net (code "48") (name "Net-(U1-PB2{slash}BOOT1)") (class "Default")
      (node (ref "R11") (pin "1") (pinfunction "1_1") (pintype "passive"))
      (node (ref "U1") (pin "20") (pinfunction "PB2/BOOT1_20") (pintype "passive"))
    )
    (net (code "49") (name "Net-(nrf1-ANT1)") (class "Default")
      (node (ref "L2") (pin "2") (pinfunction "2_2") (pintype "passive"))
      (node (ref "L3") (pin "2") (pinfunction "2_2") (pintype "passive"))
      (node (ref "nrf1") (pin "12") (pinfunction "ANT1_12") (pintype "passive"))
    )
    (net (code "50") (name "Net-(nrf1-ANT2)") (class "Default")
      (node (ref "L1") (pin "1") (pinfunction "1_1") (pintype "passive"))
      (node (ref "L2") (pin "1") (pinfunction "1_1") (pintype "passive"))
      (node (ref "nrf1") (pin "13") (pinfunction "ANT2_13") (pintype "passive"))
    )
    (net (code "51") (name "Net-(nrf1-DVDD)") (class "Default")
      (node (ref "C4") (pin "1") (pinfunction "1_1") (pintype "passive"))
      (node (ref "nrf1") (pin "19") (pinfunction "DVDD_19") (pintype "passive"))
    )
    (net (code "52") (name "Net-(nrf1-IREF)") (class "Default")
      (node (ref "R1") (pin "1") (pinfunction "1_1") (pintype "passive"))
      (node (ref "nrf1") (pin "16") (pinfunction "IREF_16") (pintype "passive"))
    )
    (net (code "53") (name "Net-(nrf1-VDD_PA)") (class "Default")
      (node (ref "C10") (pin "2") (pinfunction "2_2") (pintype "passive"))
      (node (ref "C11") (pin "2") (pinfunction "2_2") (pintype "passive"))
      (node (ref "L3") (pin "1") (pinfunction "1_1") (pintype "passive"))
      (node (ref "nrf1") (pin "11") (pinfunction "VDD_PA_11") (pintype "passive"))
    )
    (net (code "54") (name "Net-(nrf1-XC1)") (class "Default")
      (node (ref "C13") (pin "2") (pinfunction "2_2") (pintype "passive"))
      (node (ref "R8") (pin "2") (pinfunction "2_2") (pintype "passive"))
      (node (ref "XTAL1") (pin "1") (pinfunction "1_1") (pintype "passive"))
      (node (ref "nrf1") (pin "10") (pinfunction "XC1_10") (pintype "passive"))
    )
    (net (code "55") (name "Net-(nrf1-XC2)") (class "Default")
      (node (ref "C12") (pin "2") (pinfunction "2_2") (pintype "passive"))
      (node (ref "R8") (pin "1") (pinfunction "1_1") (pintype "passive"))
      (node (ref "XTAL1") (pin "3") (pinfunction "3_3") (pintype "passive"))
      (node (ref "nrf1") (pin "9") (pinfunction "XC2_9") (pintype "passive"))
    )
    (net (code "56") (name "VBAT") (class "Default")
      (node (ref "C21") (pin "2") (pinfunction "2_2") (pintype "passive"))
      (node (ref "D1") (pin "2") (pinfunction "K_2") (pintype "passive"))
      (node (ref "D2") (pin "2") (pinfunction "K_2") (pintype "passive"))
      (node (ref "D3") (pin "2") (pinfunction "K_2") (pintype "passive"))
      (node (ref "D4") (pin "2") (pinfunction "K_2") (pintype "passive"))
      (node (ref "Inductor1") (pin "1") (pinfunction "1_1") (pintype "passive"))
      (node (ref "M1") (pin "1") (pinfunction "1_1") (pintype "tri_state"))
      (node (ref "M2") (pin "1") (pinfunction "1_1") (pintype "tri_state"))
      (node (ref "M3") (pin "1") (pinfunction "1_1") (pintype "tri_state"))
      (node (ref "M4") (pin "1") (pinfunction "1_1") (pintype "tri_state"))
      (node (ref "R15") (pin "1") (pinfunction "1_1") (pintype "passive"))
      (node (ref "R2") (pin "2") (pinfunction "2_2") (pintype "passive"))
      (node (ref "SW-NO/OFF1") (pin "2") (pinfunction "2_2") (pintype "passive"))
      (node (ref "SX1") (pin "5") (pinfunction "IN_5") (pintype "passive"))
    )
    (net (code "57") (name "VBAT_IN") (class "Default")
      (node (ref "BAT1") (pin "1") (pinfunction "+_1") (pintype "passive"))
      (node (ref "SW-NO/OFF1") (pin "1") (pinfunction "1_1") (pintype "passive"))
    )
    (net (code "58") (name "unconnected-(MPU1-AUX_CL-Pad7)") (class "Default")
      (node (ref "MPU1") (pin "7") (pinfunction "AUX_CL_7") (pintype "passive"))
    )
    (net (code "59") (name "unconnected-(MPU1-AUX_DA-Pad6)") (class "Default")
      (node (ref "MPU1") (pin "6") (pinfunction "AUX_DA_6") (pintype "passive"))
    )
    (net (code "60") (name "unconnected-(MPU1-INT-Pad12)") (class "Default")
      (node (ref "MPU1") (pin "12") (pinfunction "INT_12") (pintype "passive"))
    )
    (net (code "61") (name "unconnected-(MPU1-NC-Pad2)") (class "Default")
      (node (ref "MPU1") (pin "2") (pinfunction "NC_2") (pintype "passive"))
    )
    (net (code "62") (name "unconnected-(MPU1-NC-Pad3)") (class "Default")
      (node (ref "MPU1") (pin "3") (pinfunction "NC_3") (pintype "passive"))
    )
    (net (code "63") (name "unconnected-(MPU1-NC-Pad4)") (class "Default")
      (node (ref "MPU1") (pin "4") (pinfunction "NC_4") (pintype "passive"))
    )
    (net (code "64") (name "unconnected-(MPU1-NC-Pad5)") (class "Default")
      (node (ref "MPU1") (pin "5") (pinfunction "NC_5") (pintype "passive"))
    )
    (net (code "65") (name "unconnected-(MPU1-NC-Pad14)") (class "Default")
      (node (ref "MPU1") (pin "14") (pinfunction "NC_14") (pintype "passive"))
    )
    (net (code "66") (name "unconnected-(MPU1-NC-Pad15)") (class "Default")
      (node (ref "MPU1") (pin "15") (pinfunction "NC_15") (pintype "passive"))
    )
    (net (code "67") (name "unconnected-(MPU1-NC-Pad16)") (class "Default")
      (node (ref "MPU1") (pin "16") (pinfunction "NC_16") (pintype "passive"))
    )
    (net (code "68") (name "unconnected-(MPU1-NC-Pad17)") (class "Default")
      (node (ref "MPU1") (pin "17") (pinfunction "NC_17") (pintype "passive"))
    )
    (net (code "69") (name "unconnected-(MPU1-RESV-Pad19)") (class "Default")
      (node (ref "MPU1") (pin "19") (pinfunction "RESV_19") (pintype "passive"))
    )
    (net (code "70") (name "unconnected-(MPU1-RESV-Pad21)") (class "Default")
      (node (ref "MPU1") (pin "21") (pinfunction "RESV_21") (pintype "passive"))
    )
    (net (code "71") (name "unconnected-(MPU1-RESV-Pad22)") (class "Default")
      (node (ref "MPU1") (pin "22") (pinfunction "RESV_22") (pintype "passive"))
    )
    (net (code "72") (name "unconnected-(SW-NO/OFF1-Pad3)") (class "Default")
      (node (ref "SW-NO/OFF1") (pin "3") (pinfunction "3_3") (pintype "passive"))
    )
    (net (code "73") (name "unconnected-(SX1-NC-Pad6)") (class "Default")
      (node (ref "SX1") (pin "6") (pinfunction "NC_6") (pintype "passive"))
    )
    (net (code "74") (name "unconnected-(U1-JNTRST{slash}PB4-Pad40)") (class "Default")
      (node (ref "U1") (pin "40") (pinfunction "JNTRST/PB4_40") (pintype "passive"))
    )
    (net (code "75") (name "unconnected-(U1-JTDI{slash}PA15-Pad38)") (class "Default")
      (node (ref "U1") (pin "38") (pinfunction "JTDI/PA15_38") (pintype "passive"))
    )
    (net (code "76") (name "unconnected-(U1-JTDO{slash}PB3-Pad39)") (class "Default")
      (node (ref "U1") (pin "39") (pinfunction "JTDO/PB3_39") (pintype "passive"))
    )
    (net (code "77") (name "unconnected-(U1-PA0{slash}ADC_IN0{slash}TIM2_CH1_ETR-Pad10)") (class "Default")
      (node (ref "U1") (pin "10") (pinfunction "PA0/ADC_IN0/TIM2_CH1_ETR_10") (pintype "passive"))
    )
    (net (code "78") (name "unconnected-(U1-PA12-Pad33)") (class "Default")
      (node (ref "U1") (pin "33") (pinfunction "PA12_33") (pintype "passive"))
    )
    (net (code "79") (name "unconnected-(U1-PB5-Pad41)") (class "Default")
      (node (ref "U1") (pin "41") (pinfunction "PB5_41") (pintype "passive"))
    )
    (net (code "80") (name "unconnected-(U1-SPI2_MISO{slash}PB14-Pad27)") (class "Default")
      (node (ref "U1") (pin "27") (pinfunction "SPI2_MISO/PB14_27") (pintype "passive"))
    )
    (net (code "81") (name "unconnected-(U1-SPI2_NSS{slash}PB12-Pad25)") (class "Default")
      (node (ref "U1") (pin "25") (pinfunction "SPI2_NSS/PB12_25") (pintype "passive"))
    )
    (net (code "82") (name "unconnected-(U1-SPI2_SCK{slash}PB13-Pad26)") (class "Default")
      (node (ref "U1") (pin "26") (pinfunction "SPI2_SCK/PB13_26") (pintype "passive"))
    )
    (net (code "83") (name "unconnected-(U1-TIM4_CH1{slash}I2C1_SCL{slash}PB6-Pad42)") (class "Default")
      (node (ref "U1") (pin "42") (pinfunction "TIM4_CH1/I2C1_SCL/PB6_42") (pintype "passive"))
    )
    (net (code "84") (name "unconnected-(U1-TIM4_CH2{slash}I2C1_SDA{slash}PB7-Pad43)") (class "Default")
      (node (ref "U1") (pin "43") (pinfunction "TIM4_CH2/I2C1_SDA/PB7_43") (pintype "passive"))
    )
    (net (code "85") (name "unconnected-(nrf1-VDD-Pad18)") (class "Default")
      (node (ref "nrf1") (pin "18") (pinfunction "VDD_18") (pintype "passive"))
    )
  )
)
